# Trigger.net
KiCad netlist of a schematic drawn in Altium Designer
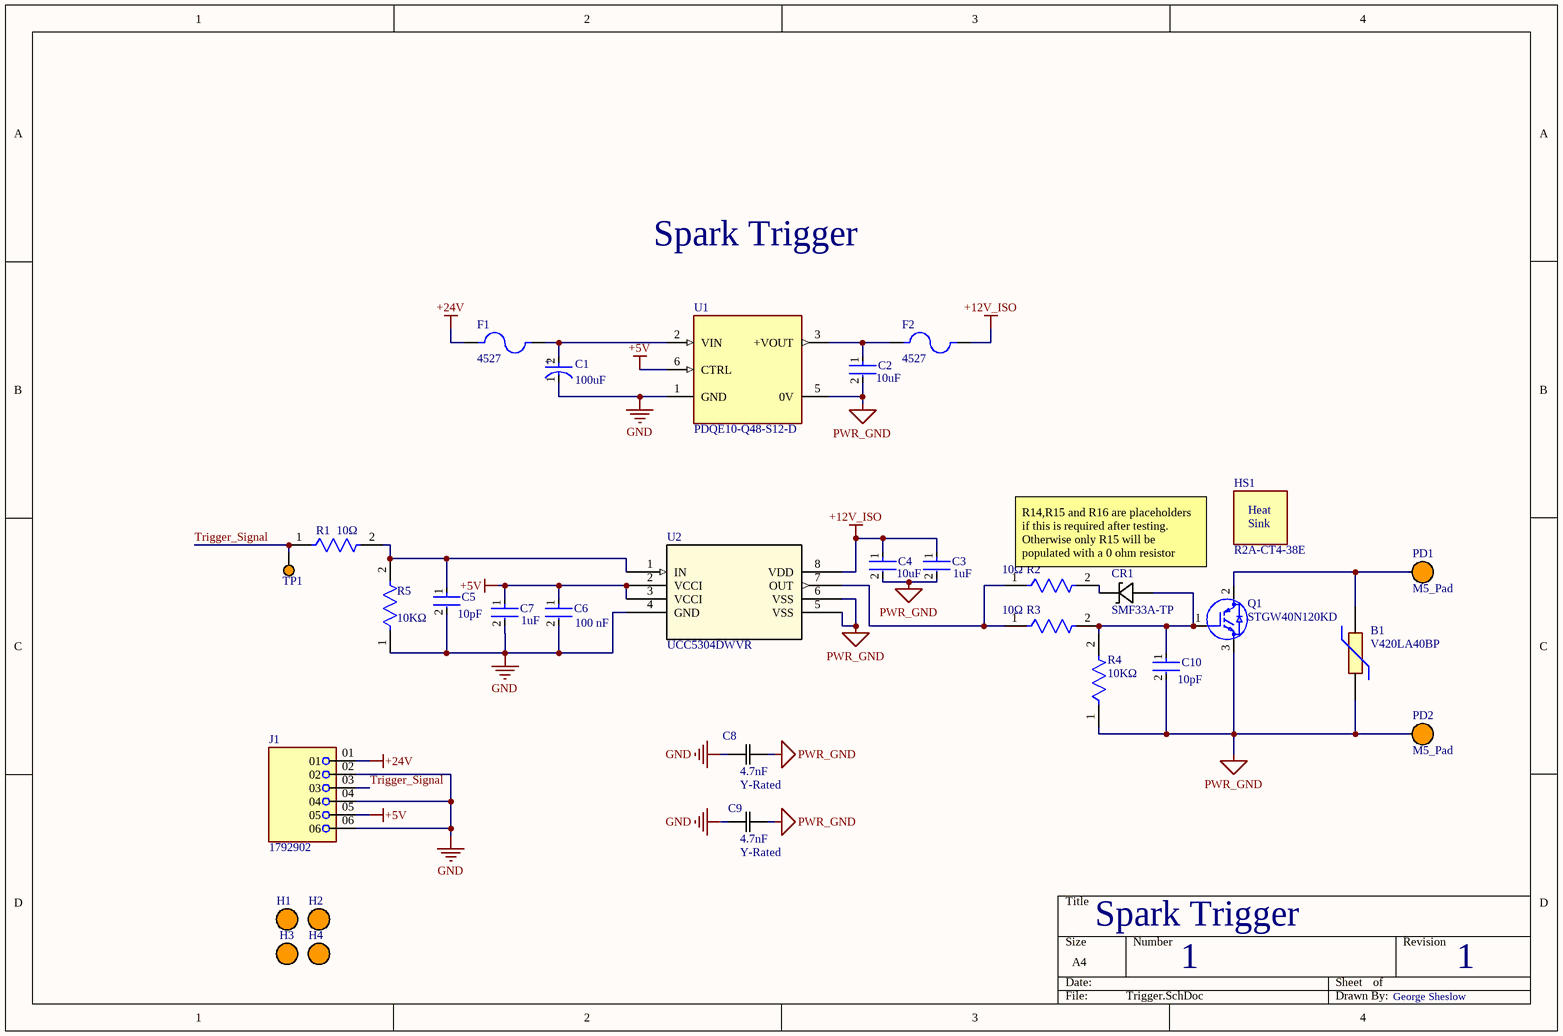
[diagram p0: Trigger.SchDoc]

(export (version "E")
  (design (tool "Eeschema 10.0.6"))
  (components
    (comp (ref "B1")
      (value "V420LA40BP")
      (footprint "V420LA40BP")
      (description "Littelfuse LA Series Variable Resistor 600pF 100A, Clamping 1060V, Varistor 610  720V")
      (fields (field (name "MOUSER PART NUMBER") "576-V420LA40BP"))
      (libsource (lib "Schlib1") (part "V420LA40BP"))
    )
    (comp (ref "C1")
      (value "EEUFM1H101")
      (footprint "FP-RAD-TH-D_8_0_5-L_11_5-MFG")
      (description "Aluminum Electrolytic Capacitors (Radial Lead Type) 100uF ±20% 50V")
      (fields (field (name "CAPACITANCE") "100uF"))
      (libsource (lib "Altium Content Vault") (part "a00bbbee19879c290e62620ae7e47b1"))
    )
    (comp (ref "C2")
      (value "CL32B106KBJNNNE")
      (footprint "FP-CL32-IPC_C")
      (description "Cap Ceramic 10uF 50V X7R ±10% SMD 1210 +125°C Embossed T/R")
      (fields
        (field (name "CAPACITANCE") "10uF")
        (field (name "TOLERANCE") "10%")
        (field (name "VOLTAGE") "50V")
      )
      (libsource (lib "Altium Content Vault") (part "b4654b650e69147ec39a6b967a45e02"))
    )
    (comp (ref "C3")
      (value "1uF")
      (footprint "FP-CC1210-GA-MFG")
      (description "CAP CER 1UF 50V X7R 1210")
      (fields
        (field (name "MANUFACTURER PART NUMBER") "CC1210KKX7R9BB105")
        (field (name "MANUFACTURER") "Yageo")
      )
      (libsource (lib "Altium Content Vault") (part "11868f565c42a9108669ba33697ecf6"))
    )
    (comp (ref "C4")
      (value "CL32B106KBJNNNE")
      (footprint "FP-CL32-IPC_C")
      (description "Cap Ceramic 10uF 50V X7R ±10% SMD 1210 +125°C Embossed T/R")
      (fields
        (field (name "CAPACITANCE") "10uF")
        (field (name "TOLERANCE") "10%")
        (field (name "VOLTAGE") "50V")
      )
      (libsource (lib "Altium Content Vault") (part "b4654b650e69147ec39a6b967a45e02"))
    )
    (comp (ref "C5")
      (value "08051A100JAT2A")
      (footprint "FP-0805-L_2_01_0_2-W_1_25-MFG")
      (description "General Purpose Ceramic Capacitor, 0805, 10pF, 5%, C0G, 30ppm/°C, 100V")
      (fields
        (field (name "VOLTAGE") "100V")
        (field (name "CAPACITANCE") "10pF")
        (field (name "TOLERANCE") "5%")
      )
      (libsource (lib "Altium Content Vault") (part "02cd4be3c70576c341d710602a673aa"))
    )
    (comp (ref "C6")
      (value "CC0805KRX7R9BB104")
      (footprint "FP-CC0805-0_85-MFG")
      (description "CAP CER 0.1UF 50V X7R 0805")
      (fields
        (field (name "TOLERANCE") "0.1")
        (field (name "CAPACITANCE") "100 nF")
        (field (name "MANUFACTURER") "Yageo")
      )
      (libsource (lib "Altium Content Vault") (part "11868f565c42a9108669ba33697ecf6"))
    )
    (comp (ref "C7")
      (value "1uF")
      (footprint "FP-CC1210-GA-MFG")
      (description "CAP CER 1UF 50V X7R 1210")
      (fields
        (field (name "MANUFACTURER PART NUMBER") "CC1210KKX7R9BB105")
        (field (name "MANUFACTURER") "Yageo")
      )
      (libsource (lib "Altium Content Vault") (part "11868f565c42a9108669ba33697ecf6"))
    )
    (comp (ref "C8")
      (value "B32021A3472M189")
      (footprint "CAP_5.0 X 11.0 X 13.0_EPC")
      (description "No Description Available")
      (fields
        (field (name "CAPACITANCE") "4.7nF")
        (field (name "RATING") "Y-Rated")
        (field (name "COPYRIGHT") "Copyright (C) 2025 Ultra Librarian. All rights reserved.")
      )
      (libsource (lib "Schlib1") (part "B32021A3472M189"))
    )
    (comp (ref "C9")
      (value "B32021A3472M189")
      (footprint "CAP_5.0 X 11.0 X 13.0_EPC")
      (description "No Description Available")
      (fields
        (field (name "CAPACITANCE") "4.7nF")
        (field (name "RATING") "Y-Rated")
        (field (name "COPYRIGHT") "Copyright (C) 2025 Ultra Librarian. All rights reserved.")
      )
      (libsource (lib "Schlib1") (part "B32021A3472M189"))
    )
    (comp (ref "C10")
      (value "08051A100JAT2A")
      (footprint "FP-0805-L_2_01_0_2-W_1_25-MFG")
      (description "General Purpose Ceramic Capacitor, 0805, 10pF, 5%, C0G, 30ppm/°C, 100V")
      (fields
        (field (name "VOLTAGE") "100V")
        (field (name "CAPACITANCE") "10pF")
        (field (name "TOLERANCE") "5%")
      )
      (libsource (lib "Altium Content Vault") (part "02cd4be3c70576c341d710602a673aa"))
    )
    (comp (ref "CR1")
      (value "SMF33A-TP")
      (footprint "SOD-123FL_MCC")
      (description "No Description Available")
      (fields (field (name "COPYRIGHT") "Copyright (C) 2025 Ultra Librarian. All rights reserved."))
      (libsource (lib "Schlib1") (part "SMF33A-TP"))
    )
    (comp (ref "F1")
      (value "4527")
      (footprint "FUSE_4527")
      (description "5mm Low Profile Holder")
      (fields (field (name "MF") "Keystone"))
      (libsource (lib "Schlib1") (part "4527"))
    )
    (comp (ref "F2")
      (value "4527")
      (footprint "FUSE_4527")
      (description "5mm Low Profile Holder")
      (fields (field (name "MF") "Keystone"))
      (libsource (lib "Schlib1") (part "4527"))
    )
    (comp (ref "H1") (value "M3_Hole") (footprint "M3_Hole") (libsource (lib "Schlib1") (part "M3_Hole")))
    (comp (ref "H2") (value "M3_Hole") (footprint "M3_Hole") (libsource (lib "Schlib1") (part "M3_Hole")))
    (comp (ref "H3") (value "M3_Hole") (footprint "M3_Hole") (libsource (lib "Schlib1") (part "M3_Hole")))
    (comp (ref "H4") (value "M3_Hole") (footprint "M3_Hole") (libsource (lib "Schlib1") (part "M3_Hole")))
    (comp (ref "HS1")
      (value "R2A-CT4-38E")
      (footprint "Heat_Sink")
      (description "Heatsink, TO-247, 8.6degC/W, 35.2 x 22 x 38mm, Spring Clip Mount ¦ Ohmite R2A-CT4-38E")
      (fields (field (name "MANUFACTURER") "Ohmite"))
      (libsource (lib "Schlib1") (part "R2A-CT4-38E"))
    )
    (comp (ref "J1")
      (value "1792902")
      (footprint "PHOENIX_1792902")
      (libsource (lib "Schlib1") (part "1792902"))
    )
    (comp (ref "PD1") (value "M5_Pad") (footprint "M5_Pad") (libsource (lib "Schlib1") (part "M5_Pad")))
    (comp (ref "PD2") (value "M5_Pad") (footprint "M5_Pad") (libsource (lib "Schlib1") (part "M5_Pad")))
    (comp (ref "Q1")
      (value "STGW40N120KD")
      (footprint "TO545P515X1560X2445-3P")
      (description "STMicroelectronics STGW40N120KD IGBT, 80 A 1200 V, 3-Pin TO-247")
      (libsource (lib "Schlib1") (part "STGW40N120KD"))
    )
    (comp (ref "R1")
      (value "10Ω")
      (footprint "FP-RT0805-MFG")
      (description "RES SMD 10 OHM 1% 1/8W 0805")
      (fields (field (name "TOLERANCE") "0.0001") (field (name "MANUFACTURER PART NUMBER") "RT0805FRE0710RL"))
      (libsource (lib "Altium Content Vault") (part "1029c3af85768c4190bb7ad29bc67b5"))
    )
    (comp (ref "R2")
      (value "10Ω")
      (footprint "FP-RT0805-MFG")
      (description "RES SMD 10 OHM 1% 1/8W 0805")
      (fields (field (name "TOLERANCE") "0.0001") (field (name "MANUFACTURER PART NUMBER") "RT0805FRE0710RL"))
      (libsource (lib "Altium Content Vault") (part "1029c3af85768c4190bb7ad29bc67b5"))
    )
    (comp (ref "R3")
      (value "10Ω")
      (footprint "FP-RT0805-MFG")
      (description "RES SMD 10 OHM 1% 1/8W 0805")
      (fields (field (name "TOLERANCE") "0.0001") (field (name "MANUFACTURER PART NUMBER") "RT0805FRE0710RL"))
      (libsource (lib "Altium Content Vault") (part "1029c3af85768c4190bb7ad29bc67b5"))
    )
    (comp (ref "R4")
      (value "10KΩ")
      (footprint "FP-RT0805-MFG")
      (description "RES 10.0K OHM 1/8W 1% SMD 0805")
      (fields
        (field (name "TOLERANCE") "0.0001")
        (field (name "OCTOPART") "https://octopart.com/rt0805fre0710kl-yageo-40301150")
      )
      (libsource (lib "Altium Content Vault") (part "1029c3af85768c4190bb7ad29bc67b5"))
    )
    (comp (ref "R5")
      (value "10KΩ")
      (footprint "FP-RT0805-MFG")
      (description "RES 10.0K OHM 1/8W 1% SMD 0805")
      (fields
        (field (name "TOLERANCE") "0.0001")
        (field (name "OCTOPART") "https://octopart.com/rt0805fre0710kl-yageo-40301150")
      )
      (libsource (lib "Altium Content Vault") (part "1029c3af85768c4190bb7ad29bc67b5"))
    )
    (comp (ref "TP1")
      (value "Test Point")
      (footprint "Test_Pad")
      (description "Just a Pad")
      (fields
        (field (name "MANUFACTURER") "Keystone Electronics")
        (field (name "MANUFACTURER PART NUMBER") "5003")
      )
      (libsource (lib "Schlib1") (part "Test Point"))
    )
    (comp (ref "U1")
      (value "PDQE10-Q48-S12-D")
      (footprint "CONV_PDQE10-Q48-S12-D")
      (description "10 W, 4:1 Input Range, Single/Dual Regulated Output, 1500 Vdc Isolation, Dc-Dc Converter")
      (fields (field (name "MF") "CUI Inc."))
      (libsource (lib "Schlib1") (part "PDQE10-Q48-S12-D"))
    )
    (comp (ref "U2")
      (value "UCC5304DWVR")
      (footprint "SOIC8_DWV_TEX")
      (fields (field (name "COPYRIGHT") "Copyright (C) 2025 Ultra Librarian. All rights reserved."))
      (libsource (lib "Schlib1") (part "UCC5304DWVR"))
    )
  )
  (nets
    (net (code "1") (name "+5V") (class "Default")
      (node (ref "C6") (pin "1") (pinfunction "1_1") (pintype "passive"))
      (node (ref "C7") (pin "1") (pinfunction "1_1") (pintype "passive"))
      (node (ref "J1") (pin "05") (pinfunction "05_05") (pintype "passive"))
      (node (ref "U1") (pin "6") (pinfunction "CTRL_6") (pintype "input"))
      (node (ref "U2") (pin "2") (pinfunction "VCCI_2") (pintype "power_in"))
      (node (ref "U2") (pin "3") (pinfunction "VCCI_3") (pintype "power_in"))
    )
    (net (code "2") (name "+12V_ISO") (class "Default")
      (node (ref "C3") (pin "1") (pinfunction "1_1") (pintype "passive"))
      (node (ref "C4") (pin "1") (pinfunction "1_1") (pintype "passive"))
      (node (ref "F2") (pin "2") (pinfunction "2_2") (pintype "passive"))
      (node (ref "U2") (pin "8") (pinfunction "VDD_8") (pintype "power_in"))
    )
    (net (code "3") (name "+24V") (class "Default")
      (node (ref "F1") (pin "1") (pinfunction "1_1") (pintype "passive"))
      (node (ref "J1") (pin "01") (pinfunction "01_01") (pintype "passive"))
    )
    (net (code "4") (name "/Trigger_Signal") (class "Default")
      (node (ref "J1") (pin "03") (pinfunction "03_03") (pintype "passive"))
      (node (ref "R1") (pin "1") (pinfunction "1_1") (pintype "passive"))
      (node (ref "TP1") (pin "1") (pinfunction "T_1") (pintype "passive"))
    )
    (net (code "5") (name "GND") (class "Default")
      (node (ref "C1") (pin "1") (pinfunction "C_1") (pintype "passive"))
      (node (ref "C5") (pin "2") (pinfunction "2_2") (pintype "passive"))
      (node (ref "C6") (pin "2") (pinfunction "2_2") (pintype "passive"))
      (node (ref "C7") (pin "2") (pinfunction "2_2") (pintype "passive"))
      (node (ref "C8") (pin "1") (pinfunction "1_1") (pintype "passive"))
      (node (ref "C9") (pin "1") (pinfunction "1_1") (pintype "passive"))
      (node (ref "J1") (pin "02") (pinfunction "02_02") (pintype "passive"))
      (node (ref "J1") (pin "04") (pinfunction "04_04") (pintype "passive"))
      (node (ref "J1") (pin "06") (pinfunction "06_06") (pintype "passive"))
      (node (ref "R5") (pin "1") (pinfunction "1_1") (pintype "passive"))
      (node (ref "U1") (pin "1") (pinfunction "GND_1") (pintype "power_in"))
      (node (ref "U2") (pin "4") (pinfunction "GND_4") (pintype "power_in"))
    )
    (net (code "6") (name "Net-(C1-A)") (class "Default")
      (node (ref "C1") (pin "2") (pinfunction "A_2") (pintype "passive"))
      (node (ref "F1") (pin "2") (pinfunction "2_2") (pintype "passive"))
      (node (ref "U1") (pin "2") (pinfunction "VIN_2") (pintype "input"))
    )
    (net (code "7") (name "Net-(CR1-Pad1)") (class "Default")
      (node (ref "CR1") (pin "1") (pinfunction "1_1") (pintype "passive"))
      (node (ref "R2") (pin "2") (pinfunction "2_2") (pintype "passive"))
    )
    (net (code "8") (name "Net-(Q1-C)") (class "Default")
      (node (ref "B1") (pin "2") (pinfunction "2_2") (pintype "passive"))
      (node (ref "PD1") (pin "1") (pinfunction "1_1") (pintype "passive"))
      (node (ref "Q1") (pin "2") (pinfunction "C_2") (pintype "passive"))
    )
    (net (code "9") (name "Net-(Q1-G)") (class "Default")
      (node (ref "C10") (pin "1") (pinfunction "1_1") (pintype "passive"))
      (node (ref "CR1") (pin "2") (pinfunction "2_2") (pintype "passive"))
      (node (ref "Q1") (pin "1") (pinfunction "G_1") (pintype "passive"))
      (node (ref "R3") (pin "2") (pinfunction "2_2") (pintype "passive"))
      (node (ref "R4") (pin "2") (pinfunction "2_2") (pintype "passive"))
    )
    (net (code "10") (name "Net-(U1-+VOUT)") (class "Default")
      (node (ref "C2") (pin "1") (pinfunction "1_1") (pintype "passive"))
      (node (ref "F2") (pin "1") (pinfunction "1_1") (pintype "passive"))
      (node (ref "U1") (pin "3") (pinfunction "+VOUT_3") (pintype "output"))
    )
    (net (code "11") (name "Net-(U2-IN)") (class "Default")
      (node (ref "C5") (pin "1") (pinfunction "1_1") (pintype "passive"))
      (node (ref "R1") (pin "2") (pinfunction "2_2") (pintype "passive"))
      (node (ref "R5") (pin "2") (pinfunction "2_2") (pintype "passive"))
      (node (ref "U2") (pin "1") (pinfunction "IN_1") (pintype "input"))
    )
    (net (code "12") (name "Net-(U2-OUT)") (class "Default")
      (node (ref "R2") (pin "1") (pinfunction "1_1") (pintype "passive"))
      (node (ref "R3") (pin "1") (pinfunction "1_1") (pintype "passive"))
      (node (ref "U2") (pin "7") (pinfunction "OUT_7") (pintype "output"))
    )
    (net (code "13") (name "PWR_GND") (class "Default")
      (node (ref "B1") (pin "1") (pinfunction "1_1") (pintype "passive"))
      (node (ref "C10") (pin "2") (pinfunction "2_2") (pintype "passive"))
      (node (ref "C2") (pin "2") (pinfunction "2_2") (pintype "passive"))
      (node (ref "C3") (pin "2") (pinfunction "2_2") (pintype "passive"))
      (node (ref "C4") (pin "2") (pinfunction "2_2") (pintype "passive"))
      (node (ref "C8") (pin "2") (pinfunction "2_2") (pintype "passive"))
      (node (ref "C9") (pin "2") (pinfunction "2_2") (pintype "passive"))
      (node (ref "PD2") (pin "1") (pinfunction "1_1") (pintype "passive"))
      (node (ref "Q1") (pin "3") (pinfunction "E_3") (pintype "passive"))
      (node (ref "R4") (pin "1") (pinfunction "1_1") (pintype "passive"))
      (node (ref "U1") (pin "5") (pinfunction "0V_5") (pintype "power_in"))
      (node (ref "U2") (pin "5") (pinfunction "VSS_5") (pintype "power_in"))
      (node (ref "U2") (pin "6") (pinfunction "VSS_6") (pintype "power_in"))
    )
  )
)
